# E-05_LPDDR4_x.net
KiCad netlist of a schematic drawn in Altium Designer
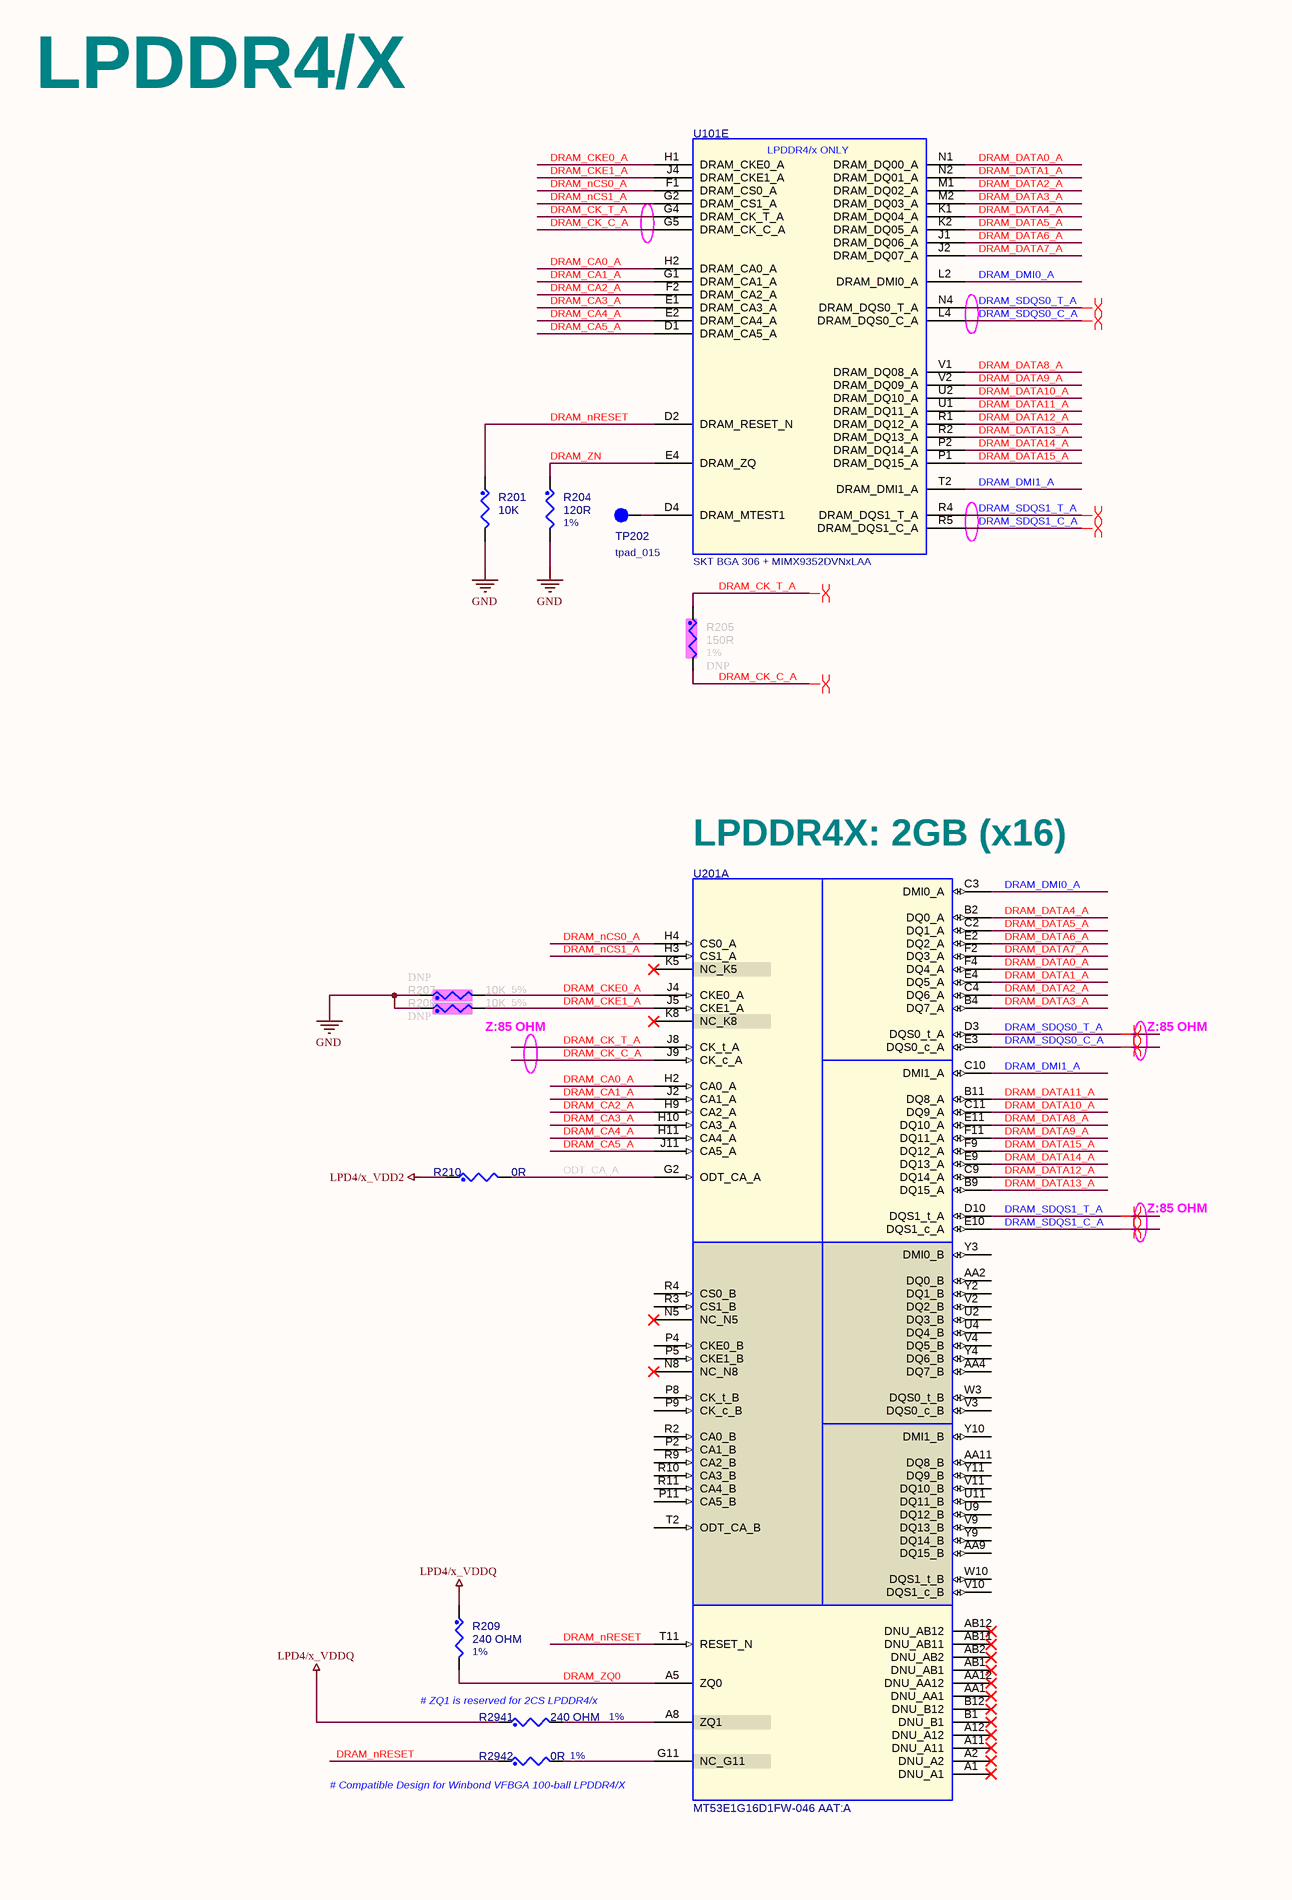
[diagram p0: E-05 LPDDR4_x.SchDoc, left]
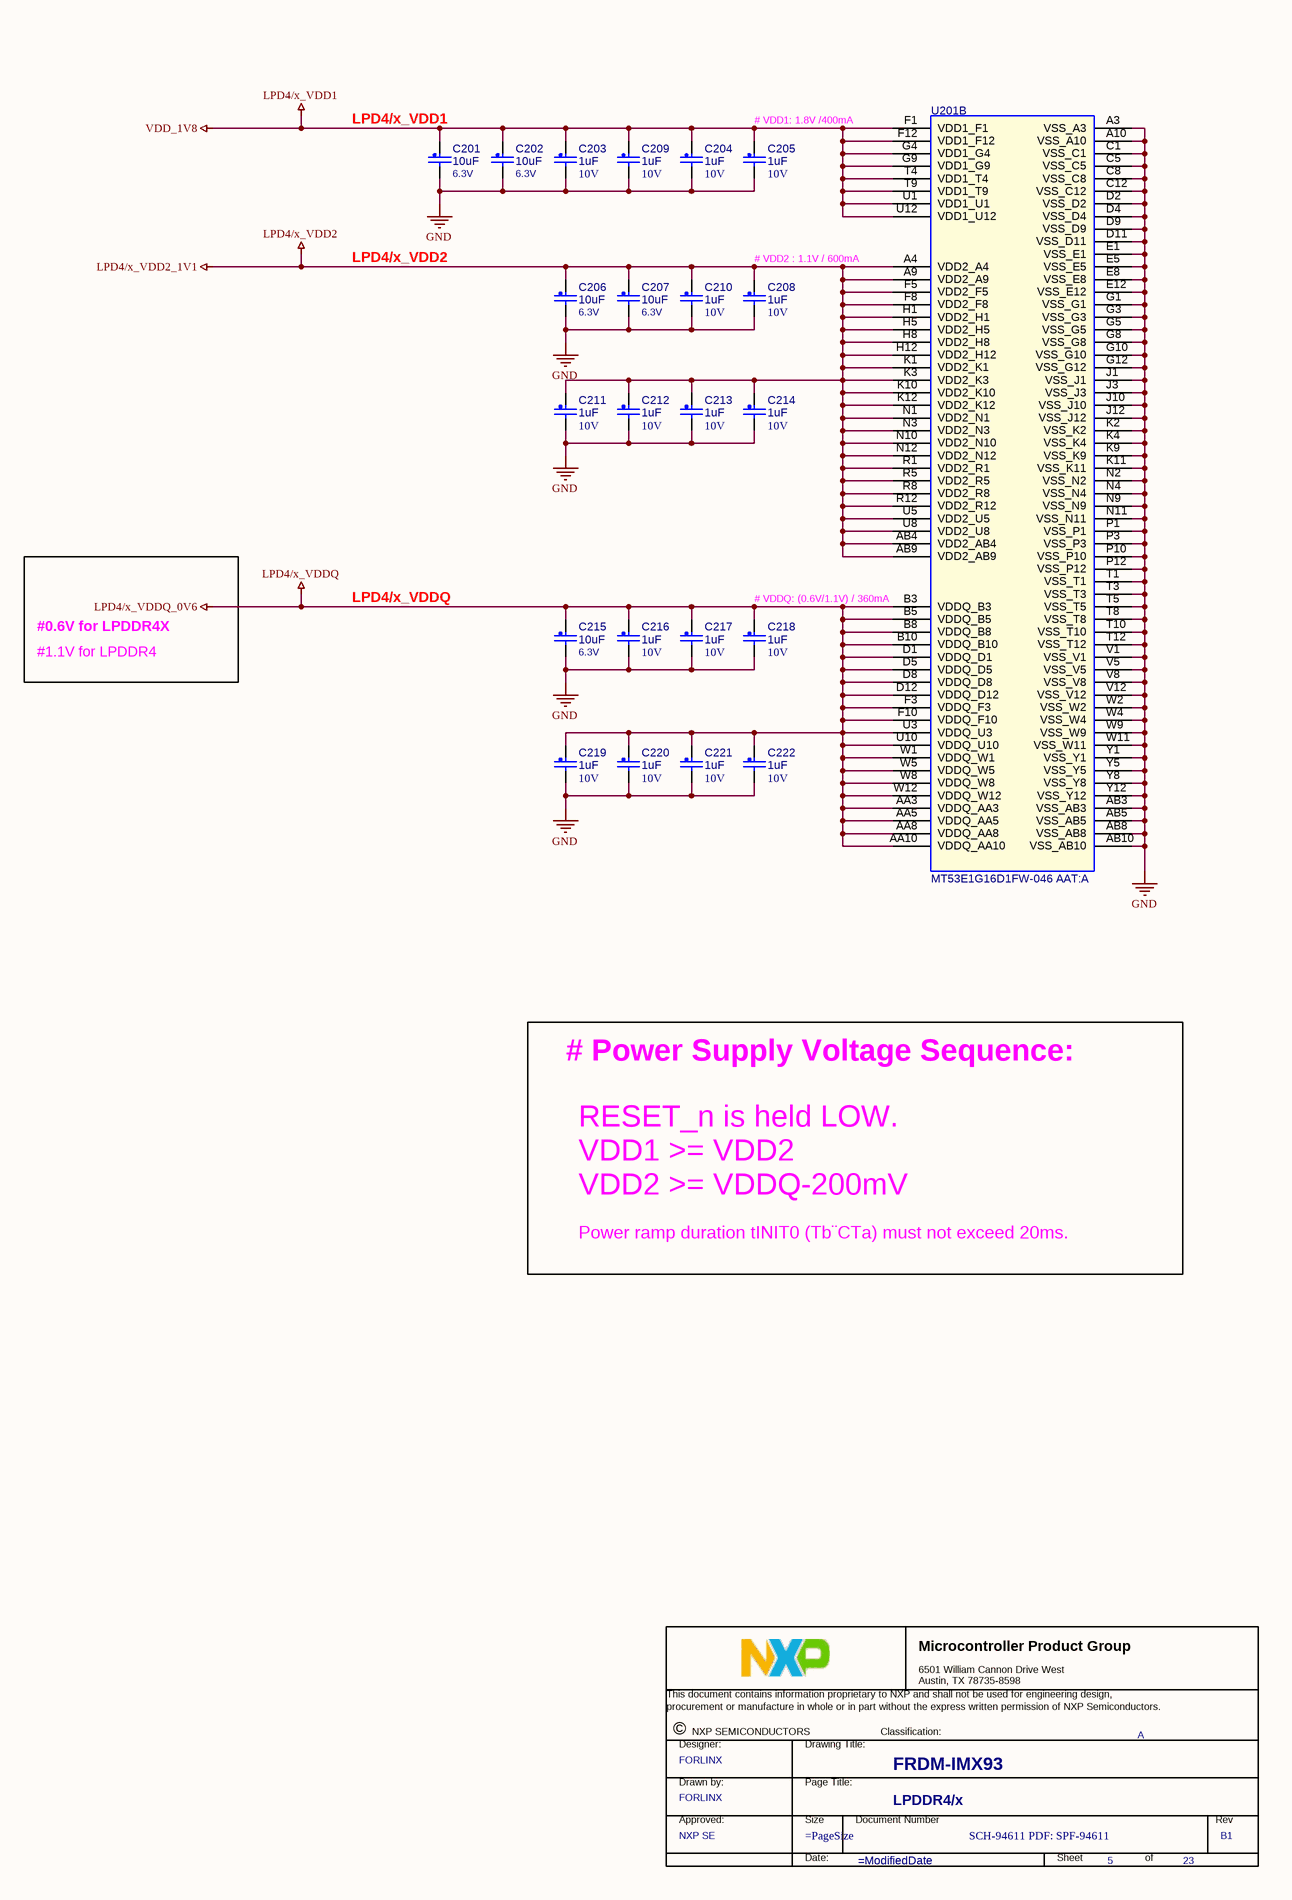
[diagram p1: E-05 LPDDR4_x.SchDoc, right]

(export (version "E")
  (design (tool "Eeschema 10.0.6"))
  (components
    (comp (ref "C201")
      (value "10uF")
      (footprint "C0402")
      (description "0402,10uF,6.3V,+/-20%,X5R")
      (fields (field (name "VOLTAGE") "6.3V") (field (name "TOLERANCE") "20%"))
      (libsource (lib "*") (part "CAP_NP"))
    )
    (comp (ref "C202")
      (value "10uF")
      (footprint "C0402")
      (description "0402,10uF,6.3V,+/-20%,X5R")
      (fields (field (name "VOLTAGE") "6.3V") (field (name "TOLERANCE") "20%"))
      (libsource (lib "*") (part "CAP_NP"))
    )
    (comp (ref "C203")
      (value "1uF")
      (footprint "C0201")
      (description "0201,1uF,10V,+/-20%,X5R")
      (fields (field (name "VOLTAGE") "10V") (field (name "TOLERANCE") "10%"))
      (libsource (lib "*") (part "CAP_NP"))
    )
    (comp (ref "C204")
      (value "1uF")
      (footprint "C0201")
      (description "0201,1uF,10V,+/-20%,X5R")
      (fields (field (name "TOLERANCE") "10%") (field (name "VOLTAGE") "10V"))
      (libsource (lib "*") (part "CAP_NP"))
    )
    (comp (ref "C205")
      (value "1uF")
      (footprint "C0201")
      (description "0201,1uF,10V,+/-20%,X5R")
      (fields (field (name "VOLTAGE") "10V") (field (name "TOLERANCE") "10%"))
      (libsource (lib "*") (part "CAP_NP"))
    )
    (comp (ref "C206")
      (value "10uF")
      (footprint "C0402")
      (description "0402,10uF,6.3V,+/-20%,X5R")
      (fields (field (name "VOLTAGE") "6.3V") (field (name "TOLERANCE") "20%"))
      (libsource (lib "*") (part "CAP_NP"))
    )
    (comp (ref "C207")
      (value "10uF")
      (footprint "C0402")
      (description "0402,10uF,6.3V,+/-20%,X5R")
      (fields (field (name "VOLTAGE") "6.3V") (field (name "TOLERANCE") "20%"))
      (libsource (lib "*") (part "CAP_NP"))
    )
    (comp (ref "C208")
      (value "1uF")
      (footprint "C0201")
      (description "0201,1uF,10V,+/-20%,X5R")
      (fields (field (name "TOLERANCE") "10%") (field (name "VOLTAGE") "10V"))
      (libsource (lib "*") (part "CAP_NP"))
    )
    (comp (ref "C209")
      (value "1uF")
      (footprint "C0201")
      (description "0201,1uF,10V,+/-20%,X5R")
      (fields (field (name "TOLERANCE") "10%") (field (name "VOLTAGE") "10V"))
      (libsource (lib "*") (part "CAP_NP"))
    )
    (comp (ref "C210")
      (value "1uF")
      (footprint "C0201")
      (description "0201,1uF,10V,+/-20%,X5R")
      (fields (field (name "TOLERANCE") "10%") (field (name "VOLTAGE") "10V"))
      (libsource (lib "*") (part "CAP_NP"))
    )
    (comp (ref "C211")
      (value "1uF")
      (footprint "C0201")
      (description "0201,1uF,10V,+/-20%,X5R")
      (fields (field (name "VOLTAGE") "10V") (field (name "TOLERANCE") "10%"))
      (libsource (lib "*") (part "CAP_NP"))
    )
    (comp (ref "C212")
      (value "1uF")
      (footprint "C0201")
      (description "0201,1uF,10V,+/-20%,X5R")
      (fields (field (name "VOLTAGE") "10V") (field (name "TOLERANCE") "10%"))
      (libsource (lib "*") (part "CAP_NP"))
    )
    (comp (ref "C213")
      (value "1uF")
      (footprint "C0201")
      (description "0201,1uF,10V,+/-20%,X5R")
      (fields (field (name "VOLTAGE") "10V") (field (name "TOLERANCE") "10%"))
      (libsource (lib "*") (part "CAP_NP"))
    )
    (comp (ref "C214")
      (value "1uF")
      (footprint "C0201")
      (description "0201,1uF,10V,+/-20%,X5R")
      (fields (field (name "TOLERANCE") "10%") (field (name "VOLTAGE") "10V"))
      (libsource (lib "*") (part "CAP_NP"))
    )
    (comp (ref "C215")
      (value "10uF")
      (footprint "C0402")
      (description "0402,10uF,6.3V,+/-20%,X5R")
      (fields (field (name "VOLTAGE") "6.3V") (field (name "TOLERANCE") "20%"))
      (libsource (lib "*") (part "CAP_NP"))
    )
    (comp (ref "C216")
      (value "1uF")
      (footprint "C0201")
      (description "0201,1uF,10V,+/-20%,X5R")
      (fields (field (name "VOLTAGE") "10V") (field (name "TOLERANCE") "10%"))
      (libsource (lib "*") (part "CAP_NP"))
    )
    (comp (ref "C217")
      (value "1uF")
      (footprint "C0201")
      (description "0201,1uF,10V,+/-20%,X5R")
      (fields (field (name "TOLERANCE") "10%") (field (name "VOLTAGE") "10V"))
      (libsource (lib "*") (part "CAP_NP"))
    )
    (comp (ref "C218")
      (value "1uF")
      (footprint "C0201")
      (description "0201,1uF,10V,+/-20%,X5R")
      (fields (field (name "VOLTAGE") "10V") (field (name "TOLERANCE") "10%"))
      (libsource (lib "*") (part "CAP_NP"))
    )
    (comp (ref "C219")
      (value "1uF")
      (footprint "C0201")
      (description "0201,1uF,10V,+/-20%,X5R")
      (fields (field (name "TOLERANCE") "10%") (field (name "VOLTAGE") "10V"))
      (libsource (lib "*") (part "CAP_NP"))
    )
    (comp (ref "C220")
      (value "1uF")
      (footprint "C0201")
      (description "0201,1uF,10V,+/-20%,X5R")
      (fields (field (name "VOLTAGE") "10V") (field (name "TOLERANCE") "10%"))
      (libsource (lib "*") (part "CAP_NP"))
    )
    (comp (ref "C221")
      (value "1uF")
      (footprint "C0201")
      (description "0201,1uF,10V,+/-20%,X5R")
      (fields (field (name "TOLERANCE") "10%") (field (name "VOLTAGE") "10V"))
      (libsource (lib "*") (part "CAP_NP"))
    )
    (comp (ref "C222")
      (value "1uF")
      (footprint "C0201")
      (description "0201,1uF,10V,+/-20%,X5R")
      (fields (field (name "VOLTAGE") "10V") (field (name "TOLERANCE") "10%"))
      (libsource (lib "*") (part "CAP_NP"))
    )
    (comp (ref "R201")
      (value "10K")
      (footprint "R0402")
      (description "0402,10K,+/-1%")
      (fields (field (name "TOLERANCE") "5%"))
      (libsource (lib "*") (part "RES"))
    )
    (comp (ref "R204")
      (value "120R")
      (footprint "R0402")
      (description "0402,120Ohm,+/-1%")
      (fields (field (name "TOLERANCE") "1%") (field (name "VOLTAGE") "1/10W"))
      (libsource (lib "*") (part "RES"))
    )
    (comp (ref "R205")
      (value "150R")
      (footprint "R0402")
      (description "0402,150Ohm,+/-5%")
      (fields (field (name "ASSY_OPT") "DNP") (field (name "TOLERANCE") "1%"))
      (libsource (lib "*") (part "RES"))
    )
    (comp (ref "R207")
      (value "10K")
      (footprint "R0402")
      (description "0402,10K,+/-1%")
      (fields (field (name "ASSY_OPT") "DNP") (field (name "TOLERANCE") "5%"))
      (libsource (lib "*") (part "RES"))
    )
    (comp (ref "R208")
      (value "10K")
      (footprint "R0402")
      (description "0402,10K,+/-1%")
      (fields (field (name "ASSY_OPT") "DNP") (field (name "TOLERANCE") "5%"))
      (libsource (lib "*") (part "RES"))
    )
    (comp (ref "R209")
      (value "240 OHM")
      (footprint "R0201")
      (description "0201,240Ohm,+/-1%")
      (fields (field (name "VOLTAGE") "25V") (field (name "TOLERANCE") "1%"))
      (libsource (lib "*") (part "RES"))
    )
    (comp (ref "R210")
      (value "0R")
      (footprint "R0402")
      (description "0402,0Ohm,+/-1%")
      (fields (field (name "VOLTAGE") "1/16W") (field (name "TOLERANCE") "5%"))
      (libsource (lib "*") (part "RES"))
    )
    (comp (ref "R2941")
      (value "240 OHM")
      (footprint "R0201")
      (description "0201,240Ohm,+/-1%")
      (fields (field (name "TOLERANCE") "1%") (field (name "VOLTAGE") "25V"))
      (libsource (lib "*") (part "RES"))
    )
    (comp (ref "R2942")
      (value "0R")
      (footprint "R0201")
      (description "0201,0Ohm,+/-5%")
      (fields (field (name "TOLERANCE") "1%") (field (name "VOLTAGE") "25V"))
      (libsource (lib "*") (part "RES"))
    )
    (comp (ref "TP202")
      (value "TPAD_015")
      (footprint "tpad_015")
      (description "no part to order")
      (fields (field (name "PCB FOOTPRINT") "tpad_015"))
      (libsource (lib "*") (part "TESTLOOP"))
    )
    (comp (ref "U101")
      (value "SKT BGA 306 + MIMX9352DVNxLAA")
      (footprint "skt_bga306_0p5_sq16p23_elast_nsp")
      (description "MIMX9352CVVXMAB,-40~105+C,11*11mm,0.5mm pitch,FCBGA,A,306pin,1.7GHz")
      (libsource (lib "*") (part "MIMX9352DVNxLAA"))
    )
    (comp (ref "U201")
      (value "MT53E1G16D1FW-046 AAT:A")
      (footprint "bga200_0p65x0p8_10x14p5")
      (description "MT53E1G16D1ZW-046 WT:C,200-ball TFBGA,10x14.5,LPDDR4/LPDDR4x,2GB,-25+C~85+C,code:D8FCP")
      (fields (field (name "VOLTAGE") "1.1V"))
      (libsource (lib "*") (part "MT53B768M32D4NQ_200P"))
    )
  )
  (nets
    (net (code "1") (name "/DRAM_CA0_A") (class "Default")
      (node (ref "U101") (pin "H2") (pinfunction "DRAM_CA0_A_H2") (pintype "passive"))
      (node (ref "U201") (pin "H2") (pinfunction "CA0_A_H2") (pintype "input"))
    )
    (net (code "2") (name "/DRAM_CA1_A") (class "Default")
      (node (ref "U101") (pin "G1") (pinfunction "DRAM_CA1_A_G1") (pintype "passive"))
      (node (ref "U201") (pin "J2") (pinfunction "CA1_A_J2") (pintype "input"))
    )
    (net (code "3") (name "/DRAM_CA2_A") (class "Default")
      (node (ref "U101") (pin "F2") (pinfunction "DRAM_CA2_A_F2") (pintype "passive"))
      (node (ref "U201") (pin "H9") (pinfunction "CA2_A_H9") (pintype "input"))
    )
    (net (code "4") (name "/DRAM_CA3_A") (class "Default")
      (node (ref "U101") (pin "E1") (pinfunction "DRAM_CA3_A_E1") (pintype "passive"))
      (node (ref "U201") (pin "H10") (pinfunction "CA3_A_H10") (pintype "input"))
    )
    (net (code "5") (name "/DRAM_CA4_A") (class "Default")
      (node (ref "U101") (pin "E2") (pinfunction "DRAM_CA4_A_E2") (pintype "passive"))
      (node (ref "U201") (pin "H11") (pinfunction "CA4_A_H11") (pintype "input"))
    )
    (net (code "6") (name "/DRAM_CA5_A") (class "Default")
      (node (ref "U101") (pin "D1") (pinfunction "DRAM_CA5_A_D1") (pintype "passive"))
      (node (ref "U201") (pin "J11") (pinfunction "CA5_A_J11") (pintype "input"))
    )
    (net (code "7") (name "/DRAM_CKE0_A") (class "Default")
      (node (ref "R207") (pin "2") (pinfunction "2_2") (pintype "passive"))
      (node (ref "U101") (pin "H1") (pinfunction "DRAM_CKE0_A_H1") (pintype "passive"))
      (node (ref "U201") (pin "J4") (pinfunction "CKE0_A_J4") (pintype "input"))
    )
    (net (code "8") (name "/DRAM_CKE1_A") (class "Default")
      (node (ref "R208") (pin "2") (pinfunction "2_2") (pintype "passive"))
      (node (ref "U101") (pin "J4") (pinfunction "DRAM_CKE1_A_J4") (pintype "passive"))
      (node (ref "U201") (pin "J5") (pinfunction "CKE1_A_J5") (pintype "input"))
    )
    (net (code "9") (name "/DRAM_CK_C_A") (class "Default")
      (node (ref "R205") (pin "2") (pinfunction "2_2") (pintype "passive"))
      (node (ref "U101") (pin "G5") (pinfunction "DRAM_CK_C_A_G5") (pintype "passive"))
      (node (ref "U201") (pin "J9") (pinfunction "CK_c_A_J9") (pintype "input"))
    )
    (net (code "10") (name "/DRAM_CK_T_A") (class "Default")
      (node (ref "R205") (pin "1") (pinfunction "1_1") (pintype "passive"))
      (node (ref "U101") (pin "G4") (pinfunction "DRAM_CK_T_A_G4") (pintype "passive"))
      (node (ref "U201") (pin "J8") (pinfunction "CK_t_A_J8") (pintype "input"))
    )
    (net (code "11") (name "/DRAM_DATA0_A") (class "Default")
      (node (ref "U101") (pin "N1") (pinfunction "DRAM_DQ00_A_N1") (pintype "passive"))
      (node (ref "U201") (pin "F4") (pinfunction "DQ4_A_F4") (pintype "bidirectional"))
    )
    (net (code "12") (name "/DRAM_DATA1_A") (class "Default")
      (node (ref "U101") (pin "N2") (pinfunction "DRAM_DQ01_A_N2") (pintype "passive"))
      (node (ref "U201") (pin "E4") (pinfunction "DQ5_A_E4") (pintype "bidirectional"))
    )
    (net (code "13") (name "/DRAM_DATA2_A") (class "Default")
      (node (ref "U101") (pin "M1") (pinfunction "DRAM_DQ02_A_M1") (pintype "passive"))
      (node (ref "U201") (pin "C4") (pinfunction "DQ6_A_C4") (pintype "bidirectional"))
    )
    (net (code "14") (name "/DRAM_DATA3_A") (class "Default")
      (node (ref "U101") (pin "M2") (pinfunction "DRAM_DQ03_A_M2") (pintype "passive"))
      (node (ref "U201") (pin "B4") (pinfunction "DQ7_A_B4") (pintype "bidirectional"))
    )
    (net (code "15") (name "/DRAM_DATA4_A") (class "Default")
      (node (ref "U101") (pin "K1") (pinfunction "DRAM_DQ04_A_K1") (pintype "passive"))
      (node (ref "U201") (pin "B2") (pinfunction "DQ0_A_B2") (pintype "bidirectional"))
    )
    (net (code "16") (name "/DRAM_DATA5_A") (class "Default")
      (node (ref "U101") (pin "K2") (pinfunction "DRAM_DQ05_A_K2") (pintype "passive"))
      (node (ref "U201") (pin "C2") (pinfunction "DQ1_A_C2") (pintype "bidirectional"))
    )
    (net (code "17") (name "/DRAM_DATA6_A") (class "Default")
      (node (ref "U101") (pin "J1") (pinfunction "DRAM_DQ06_A_J1") (pintype "passive"))
      (node (ref "U201") (pin "E2") (pinfunction "DQ2_A_E2") (pintype "bidirectional"))
    )
    (net (code "18") (name "/DRAM_DATA7_A") (class "Default")
      (node (ref "U101") (pin "J2") (pinfunction "DRAM_DQ07_A_J2") (pintype "passive"))
      (node (ref "U201") (pin "F2") (pinfunction "DQ3_A_F2") (pintype "bidirectional"))
    )
    (net (code "19") (name "/DRAM_DATA8_A") (class "Default")
      (node (ref "U101") (pin "V1") (pinfunction "DRAM_DQ08_A_V1") (pintype "passive"))
      (node (ref "U201") (pin "E11") (pinfunction "DQ10_A_E11") (pintype "bidirectional"))
    )
    (net (code "20") (name "/DRAM_DATA9_A") (class "Default")
      (node (ref "U101") (pin "V2") (pinfunction "DRAM_DQ09_A_V2") (pintype "passive"))
      (node (ref "U201") (pin "F11") (pinfunction "DQ11_A_F11") (pintype "bidirectional"))
    )
    (net (code "21") (name "/DRAM_DATA10_A") (class "Default")
      (node (ref "U101") (pin "U2") (pinfunction "DRAM_DQ10_A_U2") (pintype "passive"))
      (node (ref "U201") (pin "C11") (pinfunction "DQ9_A_C11") (pintype "bidirectional"))
    )
    (net (code "22") (name "/DRAM_DATA11_A") (class "Default")
      (node (ref "U101") (pin "U1") (pinfunction "DRAM_DQ11_A_U1") (pintype "passive"))
      (node (ref "U201") (pin "B11") (pinfunction "DQ8_A_B11") (pintype "bidirectional"))
    )
    (net (code "23") (name "/DRAM_DATA12_A") (class "Default")
      (node (ref "U101") (pin "R1") (pinfunction "DRAM_DQ12_A_R1") (pintype "passive"))
      (node (ref "U201") (pin "C9") (pinfunction "DQ14_A_C9") (pintype "bidirectional"))
    )
    (net (code "24") (name "/DRAM_DATA13_A") (class "Default")
      (node (ref "U101") (pin "R2") (pinfunction "DRAM_DQ13_A_R2") (pintype "passive"))
      (node (ref "U201") (pin "B9") (pinfunction "DQ15_A_B9") (pintype "bidirectional"))
    )
    (net (code "25") (name "/DRAM_DATA14_A") (class "Default")
      (node (ref "U101") (pin "P2") (pinfunction "DRAM_DQ14_A_P2") (pintype "passive"))
      (node (ref "U201") (pin "E9") (pinfunction "DQ13_A_E9") (pintype "bidirectional"))
    )
    (net (code "26") (name "/DRAM_DATA15_A") (class "Default")
      (node (ref "U101") (pin "P1") (pinfunction "DRAM_DQ15_A_P1") (pintype "passive"))
      (node (ref "U201") (pin "F9") (pinfunction "DQ12_A_F9") (pintype "bidirectional"))
    )
    (net (code "27") (name "/DRAM_DMI0_A") (class "Default")
      (node (ref "U101") (pin "L2") (pinfunction "DRAM_DMI0_A_L2") (pintype "passive"))
      (node (ref "U201") (pin "C3") (pinfunction "DMI0_A_C3") (pintype "bidirectional"))
    )
    (net (code "28") (name "/DRAM_DMI1_A") (class "Default")
      (node (ref "U101") (pin "T2") (pinfunction "DRAM_DMI1_A_T2") (pintype "passive"))
      (node (ref "U201") (pin "C10") (pinfunction "DMI1_A_C10") (pintype "bidirectional"))
    )
    (net (code "29") (name "/DRAM_SDQS0_C_A") (class "Default")
      (node (ref "U101") (pin "L4") (pinfunction "DRAM_DQS0_C_A_L4") (pintype "passive"))
      (node (ref "U201") (pin "E3") (pinfunction "DQS0_c_A_E3") (pintype "bidirectional"))
    )
    (net (code "30") (name "/DRAM_SDQS0_T_A") (class "Default")
      (node (ref "U101") (pin "N4") (pinfunction "DRAM_DQS0_T_A_N4") (pintype "passive"))
      (node (ref "U201") (pin "D3") (pinfunction "DQS0_t_A_D3") (pintype "bidirectional"))
    )
    (net (code "31") (name "/DRAM_SDQS1_C_A") (class "Default")
      (node (ref "U101") (pin "R5") (pinfunction "DRAM_DQS1_C_A_R5") (pintype "passive"))
      (node (ref "U201") (pin "E10") (pinfunction "DQS1_c_A_E10") (pintype "bidirectional"))
    )
    (net (code "32") (name "/DRAM_SDQS1_T_A") (class "Default")
      (node (ref "U101") (pin "R4") (pinfunction "DRAM_DQS1_T_A_R4") (pintype "passive"))
      (node (ref "U201") (pin "D10") (pinfunction "DQS1_t_A_D10") (pintype "bidirectional"))
    )
    (net (code "33") (name "/DRAM_ZN") (class "Default")
      (node (ref "R204") (pin "1") (pinfunction "1_1") (pintype "passive"))
      (node (ref "U101") (pin "E4") (pinfunction "DRAM_ZQ_E4") (pintype "passive"))
    )
    (net (code "34") (name "/DRAM_ZQ0") (class "Default")
      (node (ref "R209") (pin "2") (pinfunction "2_2") (pintype "passive"))
      (node (ref "U201") (pin "A5") (pinfunction "ZQ0_A5") (pintype "passive"))
    )
    (net (code "35") (name "/DRAM_nCS0_A") (class "Default")
      (node (ref "U101") (pin "F1") (pinfunction "DRAM_CS0_A_F1") (pintype "passive"))
      (node (ref "U201") (pin "H4") (pinfunction "CS0_A_H4") (pintype "input"))
    )
    (net (code "36") (name "/DRAM_nCS1_A") (class "Default")
      (node (ref "U101") (pin "G2") (pinfunction "DRAM_CS1_A_G2") (pintype "passive"))
      (node (ref "U201") (pin "H3") (pinfunction "CS1_A_H3") (pintype "input"))
    )
    (net (code "37") (name "/DRAM_nRESET") (class "Default")
      (node (ref "R201") (pin "1") (pinfunction "1_1") (pintype "passive"))
      (node (ref "R2942") (pin "1") (pinfunction "1_1") (pintype "passive"))
      (node (ref "U101") (pin "D2") (pinfunction "DRAM_RESET_N_D2") (pintype "passive"))
      (node (ref "U201") (pin "T11") (pinfunction "RESET_N_T11") (pintype "input"))
    )
    (net (code "38") (name "/ODT_CA_A") (class "Default")
      (node (ref "R210") (pin "2") (pinfunction "2_2") (pintype "passive"))
      (node (ref "U201") (pin "G2") (pinfunction "ODT_CA_A_G2") (pintype "input"))
    )
    (net (code "39") (name "GND") (class "Default")
      (node (ref "C201") (pin "2") (pinfunction "2_2") (pintype "passive"))
      (node (ref "C202") (pin "2") (pinfunction "2_2") (pintype "passive"))
      (node (ref "C203") (pin "2") (pinfunction "2_2") (pintype "passive"))
      (node (ref "C204") (pin "2") (pinfunction "2_2") (pintype "passive"))
      (node (ref "C205") (pin "2") (pinfunction "2_2") (pintype "passive"))
      (node (ref "C206") (pin "2") (pinfunction "2_2") (pintype "passive"))
      (node (ref "C207") (pin "2") (pinfunction "2_2") (pintype "passive"))
      (node (ref "C208") (pin "2") (pinfunction "2_2") (pintype "passive"))
      (node (ref "C209") (pin "2") (pinfunction "2_2") (pintype "passive"))
      (node (ref "C210") (pin "2") (pinfunction "2_2") (pintype "passive"))
      (node (ref "C211") (pin "2") (pinfunction "2_2") (pintype "passive"))
      (node (ref "C212") (pin "2") (pinfunction "2_2") (pintype "passive"))
      (node (ref "C213") (pin "2") (pinfunction "2_2") (pintype "passive"))
      (node (ref "C214") (pin "2") (pinfunction "2_2") (pintype "passive"))
      (node (ref "C215") (pin "2") (pinfunction "2_2") (pintype "passive"))
      (node (ref "C216") (pin "2") (pinfunction "2_2") (pintype "passive"))
      (node (ref "C217") (pin "2") (pinfunction "2_2") (pintype "passive"))
      (node (ref "C218") (pin "2") (pinfunction "2_2") (pintype "passive"))
      (node (ref "C219") (pin "2") (pinfunction "2_2") (pintype "passive"))
      (node (ref "C220") (pin "2") (pinfunction "2_2") (pintype "passive"))
      (node (ref "C221") (pin "2") (pinfunction "2_2") (pintype "passive"))
      (node (ref "C222") (pin "2") (pinfunction "2_2") (pintype "passive"))
      (node (ref "R201") (pin "2") (pinfunction "2_2") (pintype "passive"))
      (node (ref "R204") (pin "2") (pinfunction "2_2") (pintype "passive"))
      (node (ref "R207") (pin "1") (pinfunction "1_1") (pintype "passive"))
      (node (ref "R208") (pin "1") (pinfunction "1_1") (pintype "passive"))
      (node (ref "U201") (pin "A10") (pinfunction "VSS_A10_A10") (pintype "power_in"))
      (node (ref "U201") (pin "A3") (pinfunction "VSS_A3_A3") (pintype "power_in"))
      (node (ref "U201") (pin "AB10") (pinfunction "VSS_AB10_AB10") (pintype "power_in"))
      (node (ref "U201") (pin "AB3") (pinfunction "VSS_AB3_AB3") (pintype "power_in"))
      (node (ref "U201") (pin "AB5") (pinfunction "VSS_AB5_AB5") (pintype "power_in"))
      (node (ref "U201") (pin "AB8") (pinfunction "VSS_AB8_AB8") (pintype "power_in"))
      (node (ref "U201") (pin "C1") (pinfunction "VSS_C1_C1") (pintype "power_in"))
      (node (ref "U201") (pin "C12") (pinfunction "VSS_C12_C12") (pintype "power_in"))
      (node (ref "U201") (pin "C5") (pinfunction "VSS_C5_C5") (pintype "power_in"))
      (node (ref "U201") (pin "C8") (pinfunction "VSS_C8_C8") (pintype "power_in"))
      (node (ref "U201") (pin "D11") (pinfunction "VSS_D11_D11") (pintype "power_in"))
      (node (ref "U201") (pin "D2") (pinfunction "VSS_D2_D2") (pintype "power_in"))
      (node (ref "U201") (pin "D4") (pinfunction "VSS_D4_D4") (pintype "power_in"))
      (node (ref "U201") (pin "D9") (pinfunction "VSS_D9_D9") (pintype "power_in"))
      (node (ref "U201") (pin "E1") (pinfunction "VSS_E1_E1") (pintype "power_in"))
      (node (ref "U201") (pin "E12") (pinfunction "VSS_E12_E12") (pintype "power_in"))
      (node (ref "U201") (pin "E5") (pinfunction "VSS_E5_E5") (pintype "power_in"))
      (node (ref "U201") (pin "E8") (pinfunction "VSS_E8_E8") (pintype "power_in"))
      (node (ref "U201") (pin "G1") (pinfunction "VSS_G1_G1") (pintype "power_in"))
      (node (ref "U201") (pin "G10") (pinfunction "VSS_G10_G10") (pintype "power_in"))
      (node (ref "U201") (pin "G12") (pinfunction "VSS_G12_G12") (pintype "power_in"))
      (node (ref "U201") (pin "G3") (pinfunction "VSS_G3_G3") (pintype "power_in"))
      (node (ref "U201") (pin "G5") (pinfunction "VSS_G5_G5") (pintype "power_in"))
      (node (ref "U201") (pin "G8") (pinfunction "VSS_G8_G8") (pintype "power_in"))
      (node (ref "U201") (pin "J1") (pinfunction "VSS_J1_J1") (pintype "power_in"))
      (node (ref "U201") (pin "J10") (pinfunction "VSS_J10_J10") (pintype "power_in"))
      (node (ref "U201") (pin "J12") (pinfunction "VSS_J12_J12") (pintype "power_in"))
      (node (ref "U201") (pin "J3") (pinfunction "VSS_J3_J3") (pintype "power_in"))
      (node (ref "U201") (pin "K11") (pinfunction "VSS_K11_K11") (pintype "power_in"))
      (node (ref "U201") (pin "K2") (pinfunction "VSS_K2_K2") (pintype "power_in"))
      (node (ref "U201") (pin "K4") (pinfunction "VSS_K4_K4") (pintype "power_in"))
      (node (ref "U201") (pin "K9") (pinfunction "VSS_K9_K9") (pintype "power_in"))
      (node (ref "U201") (pin "N11") (pinfunction "VSS_N11_N11") (pintype "power_in"))
      (node (ref "U201") (pin "N2") (pinfunction "VSS_N2_N2") (pintype "power_in"))
      (node (ref "U201") (pin "N4") (pinfunction "VSS_N4_N4") (pintype "power_in"))
      (node (ref "U201") (pin "N9") (pinfunction "VSS_N9_N9") (pintype "power_in"))
      (node (ref "U201") (pin "P1") (pinfunction "VSS_P1_P1") (pintype "power_in"))
      (node (ref "U201") (pin "P10") (pinfunction "VSS_P10_P10") (pintype "power_in"))
      (node (ref "U201") (pin "P12") (pinfunction "VSS_P12_P12") (pintype "power_in"))
      (node (ref "U201") (pin "P3") (pinfunction "VSS_P3_P3") (pintype "power_in"))
      (node (ref "U201") (pin "T1") (pinfunction "VSS_T1_T1") (pintype "power_in"))
      (node (ref "U201") (pin "T10") (pinfunction "VSS_T10_T10") (pintype "power_in"))
      (node (ref "U201") (pin "T12") (pinfunction "VSS_T12_T12") (pintype "power_in"))
      (node (ref "U201") (pin "T3") (pinfunction "VSS_T3_T3") (pintype "power_in"))
      (node (ref "U201") (pin "T5") (pinfunction "VSS_T5_T5") (pintype "power_in"))
      (node (ref "U201") (pin "T8") (pinfunction "VSS_T8_T8") (pintype "power_in"))
      (node (ref "U201") (pin "V1") (pinfunction "VSS_V1_V1") (pintype "power_in"))
      (node (ref "U201") (pin "V12") (pinfunction "VSS_V12_V12") (pintype "power_in"))
      (node (ref "U201") (pin "V5") (pinfunction "VSS_V5_V5") (pintype "power_in"))
      (node (ref "U201") (pin "V8") (pinfunction "VSS_V8_V8") (pintype "power_in"))
      (node (ref "U201") (pin "W11") (pinfunction "VSS_W11_W11") (pintype "power_in"))
      (node (ref "U201") (pin "W2") (pinfunction "VSS_W2_W2") (pintype "power_in"))
      (node (ref "U201") (pin "W4") (pinfunction "VSS_W4_W4") (pintype "power_in"))
      (node (ref "U201") (pin "W9") (pinfunction "VSS_W9_W9") (pintype "power_in"))
      (node (ref "U201") (pin "Y1") (pinfunction "VSS_Y1_Y1") (pintype "power_in"))
      (node (ref "U201") (pin "Y12") (pinfunction "VSS_Y12_Y12") (pintype "power_in"))
      (node (ref "U201") (pin "Y5") (pinfunction "VSS_Y5_Y5") (pintype "power_in"))
      (node (ref "U201") (pin "Y8") (pinfunction "VSS_Y8_Y8") (pintype "power_in"))
    )
    (net (code "40") (name "LPD4{slash}x_VDD1") (class "Default")
      (node (ref "C201") (pin "1") (pinfunction "1_1") (pintype "passive"))
      (node (ref "C202") (pin "1") (pinfunction "1_1") (pintype "passive"))
      (node (ref "C203") (pin "1") (pinfunction "1_1") (pintype "passive"))
      (node (ref "C204") (pin "1") (pinfunction "1_1") (pintype "passive"))
      (node (ref "C205") (pin "1") (pinfunction "1_1") (pintype "passive"))
      (node (ref "C209") (pin "1") (pinfunction "1_1") (pintype "passive"))
      (node (ref "U201") (pin "F1") (pinfunction "VDD1_F1_F1") (pintype "power_in"))
      (node (ref "U201") (pin "F12") (pinfunction "VDD1_F12_F12") (pintype "power_in"))
      (node (ref "U201") (pin "G4") (pinfunction "VDD1_G4_G4") (pintype "power_in"))
      (node (ref "U201") (pin "G9") (pinfunction "VDD1_G9_G9") (pintype "power_in"))
      (node (ref "U201") (pin "T4") (pinfunction "VDD1_T4_T4") (pintype "power_in"))
      (node (ref "U201") (pin "T9") (pinfunction "VDD1_T9_T9") (pintype "power_in"))
      (node (ref "U201") (pin "U1") (pinfunction "VDD1_U1_U1") (pintype "power_in"))
      (node (ref "U201") (pin "U12") (pinfunction "VDD1_U12_U12") (pintype "power_in"))
    )
    (net (code "41") (name "LPD4{slash}x_VDD2") (class "Default")
      (node (ref "C206") (pin "1") (pinfunction "1_1") (pintype "passive"))
      (node (ref "C207") (pin "1") (pinfunction "1_1") (pintype "passive"))
      (node (ref "C208") (pin "1") (pinfunction "1_1") (pintype "passive"))
      (node (ref "C210") (pin "1") (pinfunction "1_1") (pintype "passive"))
      (node (ref "C211") (pin "1") (pinfunction "1_1") (pintype "passive"))
      (node (ref "C212") (pin "1") (pinfunction "1_1") (pintype "passive"))
      (node (ref "C213") (pin "1") (pinfunction "1_1") (pintype "passive"))
      (node (ref "C214") (pin "1") (pinfunction "1_1") (pintype "passive"))
      (node (ref "R210") (pin "1") (pinfunction "1_1") (pintype "passive"))
      (node (ref "U201") (pin "A4") (pinfunction "VDD2_A4_A4") (pintype "power_in"))
      (node (ref "U201") (pin "A9") (pinfunction "VDD2_A9_A9") (pintype "power_in"))
      (node (ref "U201") (pin "AB4") (pinfunction "VDD2_AB4_AB4") (pintype "power_in"))
      (node (ref "U201") (pin "AB9") (pinfunction "VDD2_AB9_AB9") (pintype "power_in"))
      (node (ref "U201") (pin "F5") (pinfunction "VDD2_F5_F5") (pintype "power_in"))
      (node (ref "U201") (pin "F8") (pinfunction "VDD2_F8_F8") (pintype "power_in"))
      (node (ref "U201") (pin "H1") (pinfunction "VDD2_H1_H1") (pintype "power_in"))
      (node (ref "U201") (pin "H12") (pinfunction "VDD2_H12_H12") (pintype "power_in"))
      (node (ref "U201") (pin "H5") (pinfunction "VDD2_H5_H5") (pintype "power_in"))
      (node (ref "U201") (pin "H8") (pinfunction "VDD2_H8_H8") (pintype "power_in"))
      (node (ref "U201") (pin "K1") (pinfunction "VDD2_K1_K1") (pintype "power_in"))
      (node (ref "U201") (pin "K10") (pinfunction "VDD2_K10_K10") (pintype "power_in"))
      (node (ref "U201") (pin "K12") (pinfunction "VDD2_K12_K12") (pintype "power_in"))
      (node (ref "U201") (pin "K3") (pinfunction "VDD2_K3_K3") (pintype "power_in"))
      (node (ref "U201") (pin "N1") (pinfunction "VDD2_N1_N1") (pintype "power_in"))
      (node (ref "U201") (pin "N10") (pinfunction "VDD2_N10_N10") (pintype "power_in"))
      (node (ref "U201") (pin "N12") (pinfunction "VDD2_N12_N12") (pintype "power_in"))
      (node (ref "U201") (pin "N3") (pinfunction "VDD2_N3_N3") (pintype "power_in"))
      (node (ref "U201") (pin "R1") (pinfunction "VDD2_R1_R1") (pintype "power_in"))
      (node (ref "U201") (pin "R12") (pinfunction "VDD2_R12_R12") (pintype "power_in"))
      (node (ref "U201") (pin "R5") (pinfunction "VDD2_R5_R5") (pintype "power_in"))
      (node (ref "U201") (pin "R8") (pinfunction "VDD2_R8_R8") (pintype "power_in"))
      (node (ref "U201") (pin "U5") (pinfunction "VDD2_U5_U5") (pintype "power_in"))
      (node (ref "U201") (pin "U8") (pinfunction "VDD2_U8_U8") (pintype "power_in"))
    )
    (net (code "42") (name "LPD4{slash}x_VDDQ") (class "Default")
      (node (ref "C215") (pin "1") (pinfunction "1_1") (pintype "passive"))
      (node (ref "C216") (pin "1") (pinfunction "1_1") (pintype "passive"))
      (node (ref "C217") (pin "1") (pinfunction "1_1") (pintype "passive"))
      (node (ref "C218") (pin "1") (pinfunction "1_1") (pintype "passive"))
      (node (ref "C219") (pin "1") (pinfunction "1_1") (pintype "passive"))
      (node (ref "C220") (pin "1") (pinfunction "1_1") (pintype "passive"))
      (node (ref "C221") (pin "1") (pinfunction "1_1") (pintype "passive"))
      (node (ref "C222") (pin "1") (pinfunction "1_1") (pintype "passive"))
      (node (ref "R209") (pin "1") (pinfunction "1_1") (pintype "passive"))
      (node (ref "R2941") (pin "1") (pinfunction "1_1") (pintype "passive"))
      (node (ref "U201") (pin "AA10") (pinfunction "VDDQ_AA10_AA10") (pintype "power_in"))
      (node (ref "U201") (pin "AA3") (pinfunction "VDDQ_AA3_AA3") (pintype "power_in"))
      (node (ref "U201") (pin "AA5") (pinfunction "VDDQ_AA5_AA5") (pintype "power_in"))
      (node (ref "U201") (pin "AA8") (pinfunction "VDDQ_AA8_AA8") (pintype "power_in"))
      (node (ref "U201") (pin "B10") (pinfunction "VDDQ_B10_B10") (pintype "power_in"))
      (node (ref "U201") (pin "B3") (pinfunction "VDDQ_B3_B3") (pintype "power_in"))
      (node (ref "U201") (pin "B5") (pinfunction "VDDQ_B5_B5") (pintype "power_in"))
      (node (ref "U201") (pin "B8") (pinfunction "VDDQ_B8_B8") (pintype "power_in"))
      (node (ref "U201") (pin "D1") (pinfunction "VDDQ_D1_D1") (pintype "power_in"))
      (node (ref "U201") (pin "D12") (pinfunction "VDDQ_D12_D12") (pintype "power_in"))
      (node (ref "U201") (pin "D5") (pinfunction "VDDQ_D5_D5") (pintype "power_in"))
      (node (ref "U201") (pin "D8") (pinfunction "VDDQ_D8_D8") (pintype "power_in"))
      (node (ref "U201") (pin "F10") (pinfunction "VDDQ_F10_F10") (pintype "power_in"))
      (node (ref "U201") (pin "F3") (pinfunction "VDDQ_F3_F3") (pintype "power_in"))
      (node (ref "U201") (pin "U10") (pinfunction "VDDQ_U10_U10") (pintype "power_in"))
      (node (ref "U201") (pin "U3") (pinfunction "VDDQ_U3_U3") (pintype "power_in"))
      (node (ref "U201") (pin "W1") (pinfunction "VDDQ_W1_W1") (pintype "power_in"))
      (node (ref "U201") (pin "W12") (pinfunction "VDDQ_W12_W12") (pintype "power_in"))
      (node (ref "U201") (pin "W5") (pinfunction "VDDQ_W5_W5") (pintype "power_in"))
      (node (ref "U201") (pin "W8") (pinfunction "VDDQ_W8_W8") (pintype "power_in"))
    )
    (net (code "43") (name "Net-(TP202-Pin1)") (class "Default")
      (node (ref "TP202") (pin "1") (pinfunction "Pin1_1") (pintype "passive"))
      (node (ref "U101") (pin "D4") (pinfunction "DRAM_MTEST1_D4") (pintype "passive"))
    )
    (net (code "44") (name "Net-(U201A-NC_G11)") (class "Default")
      (node (ref "R2942") (pin "2") (pinfunction "2_2") (pintype "passive"))
      (node (ref "U201") (pin "G11") (pinfunction "NC_G11_G11") (pintype "passive"))
    )
    (net (code "45") (name "Net-(U201A-ZQ1)") (class "Default")
      (node (ref "R2941") (pin "2") (pinfunction "2_2") (pintype "passive"))
      (node (ref "U201") (pin "A8") (pinfunction "ZQ1_A8") (pintype "passive"))
    )
    (net (code "46") (name "unconnected-(U201A-CA0_B-PadR2)") (class "Default")
      (node (ref "U201") (pin "R2") (pinfunction "CA0_B_R2") (pintype "input"))
    )
    (net (code "47") (name "unconnected-(U201A-CA1_B-PadP2)") (class "Default")
      (node (ref "U201") (pin "P2") (pinfunction "CA1_B_P2") (pintype "input"))
    )
    (net (code "48") (name "unconnected-(U201A-CA2_B-PadR9)") (class "Default")
      (node (ref "U201") (pin "R9") (pinfunction "CA2_B_R9") (pintype "input"))
    )
    (net (code "49") (name "unconnected-(U201A-CA3_B-PadR10)") (class "Default")
      (node (ref "U201") (pin "R10") (pinfunction "CA3_B_R10") (pintype "input"))
    )
    (net (code "50") (name "unconnected-(U201A-CA4_B-PadR11)") (class "Default")
      (node (ref "U201") (pin "R11") (pinfunction "CA4_B_R11") (pintype "input"))
    )
    (net (code "51") (name "unconnected-(U201A-CA5_B-PadP11)") (class "Default")
      (node (ref "U201") (pin "P11") (pinfunction "CA5_B_P11") (pintype "input"))
    )
    (net (code "52") (name "unconnected-(U201A-CKE0_B-PadP4)") (class "Default")
      (node (ref "U201") (pin "P4") (pinfunction "CKE0_B_P4") (pintype "input"))
    )
    (net (code "53") (name "unconnected-(U201A-CKE1_B-PadP5)") (class "Default")
      (node (ref "U201") (pin "P5") (pinfunction "CKE1_B_P5") (pintype "input"))
    )
    (net (code "54") (name "unconnected-(U201A-CK_c_B-PadP9)") (class "Default")
      (node (ref "U201") (pin "P9") (pinfunction "CK_c_B_P9") (pintype "input"))
    )
    (net (code "55") (name "unconnected-(U201A-CK_t_B-PadP8)") (class "Default")
      (node (ref "U201") (pin "P8") (pinfunction "CK_t_B_P8") (pintype "input"))
    )
    (net (code "56") (name "unconnected-(U201A-CS0_B-PadR4)") (class "Default")
      (node (ref "U201") (pin "R4") (pinfunction "CS0_B_R4") (pintype "input"))
    )
    (net (code "57") (name "unconnected-(U201A-CS1_B-PadR3)") (class "Default")
      (node (ref "U201") (pin "R3") (pinfunction "CS1_B_R3") (pintype "input"))
    )
    (net (code "58") (name "unconnected-(U201A-DMI0_B-PadY3)") (class "Default")
      (node (ref "U201") (pin "Y3") (pinfunction "DMI0_B_Y3") (pintype "bidirectional"))
    )
    (net (code "59") (name "unconnected-(U201A-DMI1_B-PadY10)") (class "Default")
      (node (ref "U201") (pin "Y10") (pinfunction "DMI1_B_Y10") (pintype "bidirectional"))
    )
    (net (code "60") (name "unconnected-(U201A-DNU_A1-PadA1)") (class "Default")
      (node (ref "U201") (pin "A1") (pinfunction "DNU_A1_A1") (pintype "passive+no_connect"))
    )
    (net (code "61") (name "unconnected-(U201A-DNU_A2-PadA2)") (class "Default")
      (node (ref "U201") (pin "A2") (pinfunction "DNU_A2_A2") (pintype "passive+no_connect"))
    )
    (net (code "62") (name "unconnected-(U201A-DNU_A11-PadA11)") (class "Default")
      (node (ref "U201") (pin "A11") (pinfunction "DNU_A11_A11") (pintype "passive+no_connect"))
    )
    (net (code "63") (name "unconnected-(U201A-DNU_A12-PadA12)") (class "Default")
      (node (ref "U201") (pin "A12") (pinfunction "DNU_A12_A12") (pintype "passive+no_connect"))
    )
    (net (code "64") (name "unconnected-(U201A-DNU_AA1-PadAA1)") (class "Default")
      (node (ref "U201") (pin "AA1") (pinfunction "DNU_AA1_AA1") (pintype "passive+no_connect"))
    )
    (net (code "65") (name "unconnected-(U201A-DNU_AA12-PadAA12)") (class "Default")
      (node (ref "U201") (pin "AA12") (pinfunction "DNU_AA12_AA12") (pintype "passive+no_connect"))
    )
    (net (code "66") (name "unconnected-(U201A-DNU_AB1-PadAB1)") (class "Default")
      (node (ref "U201") (pin "AB1") (pinfunction "DNU_AB1_AB1") (pintype "passive+no_connect"))
    )
    (net (code "67") (name "unconnected-(U201A-DNU_AB2-PadAB2)") (class "Default")
      (node (ref "U201") (pin "AB2") (pinfunction "DNU_AB2_AB2") (pintype "passive+no_connect"))
    )
    (net (code "68") (name "unconnected-(U201A-DNU_AB11-PadAB11)") (class "Default")
      (node (ref "U201") (pin "AB11") (pinfunction "DNU_AB11_AB11") (pintype "passive+no_connect"))
    )
    (net (code "69") (name "unconnected-(U201A-DNU_AB12-PadAB12)") (class "Default")
      (node (ref "U201") (pin "AB12") (pinfunction "DNU_AB12_AB12") (pintype "passive+no_connect"))
    )
    (net (code "70") (name "unconnected-(U201A-DNU_B1-PadB1)") (class "Default")
      (node (ref "U201") (pin "B1") (pinfunction "DNU_B1_B1") (pintype "passive+no_connect"))
    )
    (net (code "71") (name "unconnected-(U201A-DNU_B12-PadB12)") (class "Default")
      (node (ref "U201") (pin "B12") (pinfunction "DNU_B12_B12") (pintype "passive+no_connect"))
    )
    (net (code "72") (name "unconnected-(U201A-DQ0_B-PadAA2)") (class "Default")
      (node (ref "U201") (pin "AA2") (pinfunction "DQ0_B_AA2") (pintype "bidirectional"))
    )
    (net (code "73") (name "unconnected-(U201A-DQ1_B-PadY2)") (class "Default")
      (node (ref "U201") (pin "Y2") (pinfunction "DQ1_B_Y2") (pintype "bidirectional"))
    )
    (net (code "74") (name "unconnected-(U201A-DQ2_B-PadV2)") (class "Default")
      (node (ref "U201") (pin "V2") (pinfunction "DQ2_B_V2") (pintype "bidirectional"))
    )
    (net (code "75") (name "unconnected-(U201A-DQ3_B-PadU2)") (class "Default")
      (node (ref "U201") (pin "U2") (pinfunction "DQ3_B_U2") (pintype "bidirectional"))
    )
    (net (code "76") (name "unconnected-(U201A-DQ4_B-PadU4)") (class "Default")
      (node (ref "U201") (pin "U4") (pinfunction "DQ4_B_U4") (pintype "bidirectional"))
    )
    (net (code "77") (name "unconnected-(U201A-DQ5_B-PadV4)") (class "Default")
      (node (ref "U201") (pin "V4") (pinfunction "DQ5_B_V4") (pintype "bidirectional"))
    )
    (net (code "78") (name "unconnected-(U201A-DQ6_B-PadY4)") (class "Default")
      (node (ref "U201") (pin "Y4") (pinfunction "DQ6_B_Y4") (pintype "bidirectional"))
    )
    (net (code "79") (name "unconnected-(U201A-DQ7_B-PadAA4)") (class "Default")
      (node (ref "U201") (pin "AA4") (pinfunction "DQ7_B_AA4") (pintype "bidirectional"))
    )
    (net (code "80") (name "unconnected-(U201A-DQ8_B-PadAA11)") (class "Default")
      (node (ref "U201") (pin "AA11") (pinfunction "DQ8_B_AA11") (pintype "bidirectional"))
    )
    (net (code "81") (name "unconnected-(U201A-DQ9_B-PadY11)") (class "Default")
      (node (ref "U201") (pin "Y11") (pinfunction "DQ9_B_Y11") (pintype "bidirectional"))
    )
    (net (code "82") (name "unconnected-(U201A-DQ10_B-PadV11)") (class "Default")
      (node (ref "U201") (pin "V11") (pinfunction "DQ10_B_V11") (pintype "bidirectional"))
    )
    (net (code "83") (name "unconnected-(U201A-DQ11_B-PadU11)") (class "Default")
      (node (ref "U201") (pin "U11") (pinfunction "DQ11_B_U11") (pintype "bidirectional"))
    )
    (net (code "84") (name "unconnected-(U201A-DQ12_B-PadU9)") (class "Default")
      (node (ref "U201") (pin "U9") (pinfunction "DQ12_B_U9") (pintype "bidirectional"))
    )
    (net (code "85") (name "unconnected-(U201A-DQ13_B-PadV9)") (class "Default")
      (node (ref "U201") (pin "V9") (pinfunction "DQ13_B_V9") (pintype "bidirectional"))
    )
    (net (code "86") (name "unconnected-(U201A-DQ14_B-PadY9)") (class "Default")
      (node (ref "U201") (pin "Y9") (pinfunction "DQ14_B_Y9") (pintype "bidirectional"))
    )
    (net (code "87") (name "unconnected-(U201A-DQ15_B-PadAA9)") (class "Default")
      (node (ref "U201") (pin "AA9") (pinfunction "DQ15_B_AA9") (pintype "bidirectional"))
    )
    (net (code "88") (name "unconnected-(U201A-DQS0_c_B-PadV3)") (class "Default")
      (node (ref "U201") (pin "V3") (pinfunction "DQS0_c_B_V3") (pintype "bidirectional"))
    )
    (net (code "89") (name "unconnected-(U201A-DQS0_t_B-PadW3)") (class "Default")
      (node (ref "U201") (pin "W3") (pinfunction "DQS0_t_B_W3") (pintype "bidirectional"))
    )
    (net (code "90") (name "unconnected-(U201A-DQS1_c_B-PadV10)") (class "Default")
      (node (ref "U201") (pin "V10") (pinfunction "DQS1_c_B_V10") (pintype "bidirectional"))
    )
    (net (code "91") (name "unconnected-(U201A-DQS1_t_B-PadW10)") (class "Default")
      (node (ref "U201") (pin "W10") (pinfunction "DQS1_t_B_W10") (pintype "bidirectional"))
    )
    (net (code "92") (name "unconnected-(U201A-NC_K5-PadK5)") (class "Default")
      (node (ref "U201") (pin "K5") (pinfunction "NC_K5_K5") (pintype "passive+no_connect"))
    )
    (net (code "93") (name "unconnected-(U201A-NC_K8-PadK8)") (class "Default")
      (node (ref "U201") (pin "K8") (pinfunction "NC_K8_K8") (pintype "passive+no_connect"))
    )
    (net (code "94") (name "unconnected-(U201A-NC_N5-PadN5)") (class "Default")
      (node (ref "U201") (pin "N5") (pinfunction "NC_N5_N5") (pintype "passive+no_connect"))
    )
    (net (code "95") (name "unconnected-(U201A-NC_N8-PadN8)") (class "Default")
      (node (ref "U201") (pin "N8") (pinfunction "NC_N8_N8") (pintype "passive+no_connect"))
    )
    (net (code "96") (name "unconnected-(U201A-ODT_CA_B-PadT2)") (class "Default")
      (node (ref "U201") (pin "T2") (pinfunction "ODT_CA_B_T2") (pintype "input"))
    )
  )
)
